# Qwiic_Grideye.net
KiCad netlist of a schematic drawn in EAGLE
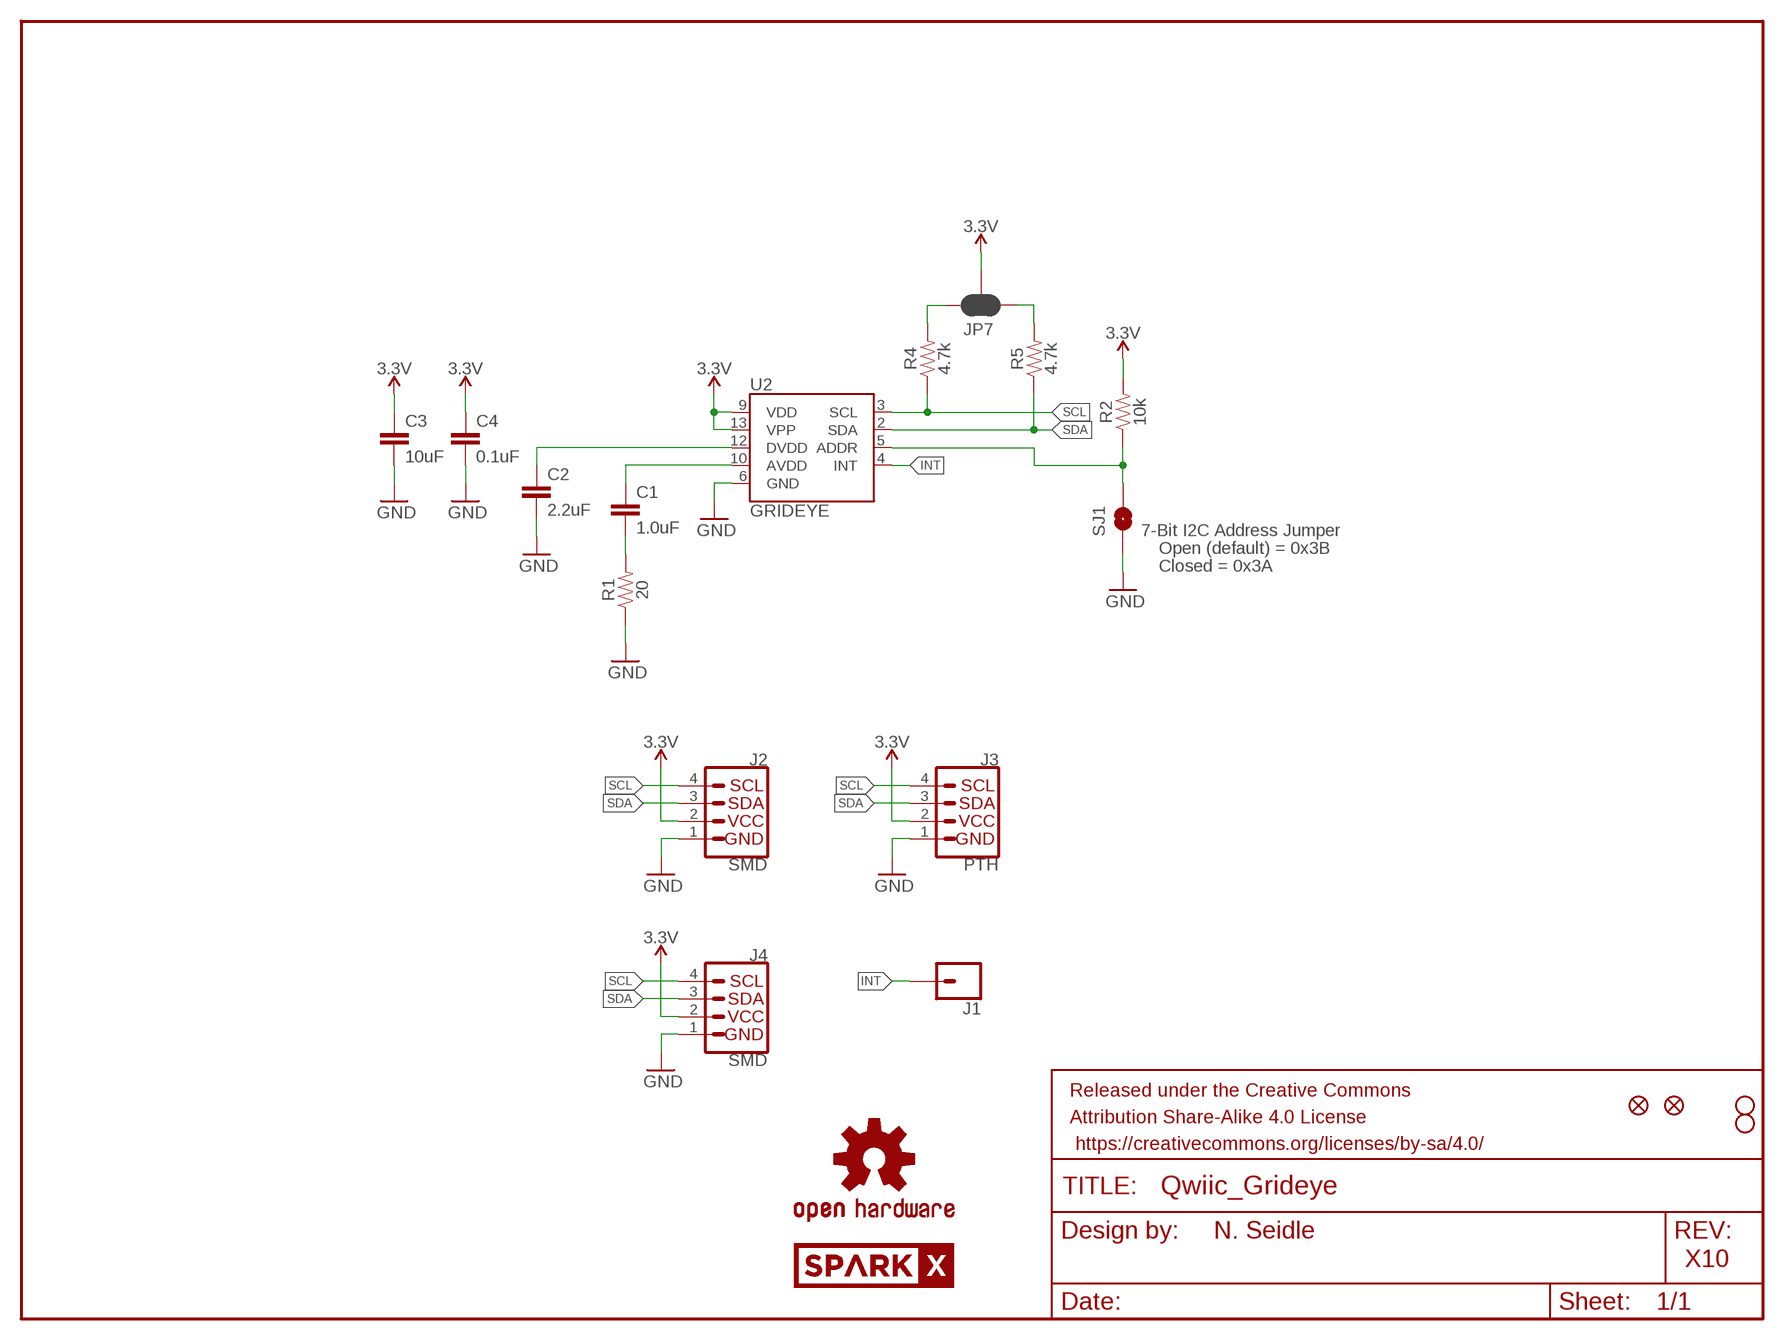
[diagram p0: schematic, sheet 1]

(export (version "E")
  (design (tool "Eeschema 10.0.6"))
  (components
    (comp (ref "C1")
      (value "1.0uF")
      (footprint "eagle-import:0603")
      (libsource (lib "eagle-import") (part "1.0UF-0603-16V-10%"))
    )
    (comp (ref "C2")
      (value "2.2uF")
      (footprint "eagle-import:0603")
      (libsource (lib "eagle-import") (part "2.2UF-0603-10V-20%"))
    )
    (comp (ref "C3")
      (value "10uF")
      (footprint "eagle-import:0603")
      (libsource (lib "eagle-import") (part "10UF-0603-6.3V-20%"))
    )
    (comp (ref "C4")
      (value "0.1uF")
      (footprint "eagle-import:0603")
      (libsource (lib "eagle-import") (part "0.1UF-0603-25V-(+80/-20%)"))
    )
    (comp (ref "FRAME1")
      (value "FRAME-LETTER")
      (footprint "eagle-import:CREATIVE_COMMONS")
      (libsource (lib "eagle-import") (part "FRAME-LETTER"))
    )
    (comp (ref "J1")
      (value "CONN_01PTH_NO_SILK_YES_STOP")
      (footprint "eagle-import:1X01_NO_SILK")
      (libsource (lib "eagle-import") (part "CONN_01PTH_NO_SILK_YES_STOP"))
    )
    (comp (ref "J2")
      (value "SMD")
      (footprint "eagle-import:1X04_1MM_RA")
      (libsource (lib "eagle-import") (part "I2C_STANDARDJS-1MM"))
    )
    (comp (ref "J3")
      (value "PTH")
      (footprint "eagle-import:1X04_NO_SILK")
      (libsource (lib "eagle-import") (part "I2C_STANDARD_NO_SILK"))
    )
    (comp (ref "J4")
      (value "SMD")
      (footprint "eagle-import:1X04_1MM_RA")
      (libsource (lib "eagle-import") (part "I2C_STANDARDJS-1MM"))
    )
    (comp (ref "JP2")
      (value "FIDUCIALUFIDUCIAL")
      (footprint "eagle-import:MICRO-FIDUCIAL")
      (libsource (lib "eagle-import") (part "FIDUCIALUFIDUCIAL"))
    )
    (comp (ref "JP3")
      (value "STAND-OFF")
      (footprint "eagle-import:STAND-OFF")
      (libsource (lib "eagle-import") (part "STAND-OFF"))
    )
    (comp (ref "JP4")
      (value "STAND-OFF")
      (footprint "eagle-import:STAND-OFF")
      (libsource (lib "eagle-import") (part "STAND-OFF"))
    )
    (comp (ref "JP6")
      (value "FIDUCIALUFIDUCIAL")
      (footprint "eagle-import:MICRO-FIDUCIAL")
      (libsource (lib "eagle-import") (part "FIDUCIALUFIDUCIAL"))
    )
    (comp (ref "JP7")
      (value "JUMPER-SMT_3_2-NC_PASTE_SILK")
      (footprint "eagle-import:SMT-JUMPER_3_2-NC_PASTE_SILK")
      (libsource (lib "eagle-import") (part "JUMPER-SMT_3_2-NC_PASTE_SILK"))
    )
    (comp (ref "LOGO1")
      (value "OSHW-LOGOMINI")
      (footprint "eagle-import:OSHW-LOGO-MINI")
      (libsource (lib "eagle-import") (part "OSHW-LOGOMINI"))
    )
    (comp (ref "R1")
      (value "20")
      (footprint "eagle-import:0603")
      (libsource (lib "eagle-import") (part "20OHM-0603-1/10W-1%"))
    )
    (comp (ref "R2")
      (value "10k")
      (footprint "eagle-import:0603")
      (libsource (lib "eagle-import") (part "10KOHM-0603-1/10W-1%"))
    )
    (comp (ref "R4")
      (value "4.7k")
      (footprint "eagle-import:0603")
      (libsource (lib "eagle-import") (part "4.7KOHM-0603-1/10W-1%"))
    )
    (comp (ref "R5")
      (value "4.7k")
      (footprint "eagle-import:0603")
      (libsource (lib "eagle-import") (part "4.7KOHM-0603-1/10W-1%"))
    )
    (comp (ref "SJ1")
      (value "SOLDERJUMPERNO")
      (footprint "eagle-import:SJ_2S-NO")
      (libsource (lib "eagle-import") (part "SOLDERJUMPERNO"))
    )
    (comp (ref "U$1")
      (value "SPARKX-LOGO4")
      (footprint "eagle-import:SPARKX-MEDIUM")
      (libsource (lib "eagle-import") (part "SPARKX-LOGO4"))
    )
    (comp (ref "U$2")
      (value "SPARKX-LOGO4")
      (footprint "eagle-import:SPARKX-MEDIUM")
      (libsource (lib "eagle-import") (part "SPARKX-LOGO4"))
    )
    (comp (ref "U2")
      (value "GRIDEYE")
      (footprint "eagle-import:GRIDEYE-AMG88")
      (libsource (lib "eagle-import") (part "GRIDEYE"))
    )
  )
  (nets
    (net (code "1") (name "3.3V") (class "Default")
      (node (ref "C3") (pin "1") (pinfunction "1_1") (pintype "passive"))
      (node (ref "C4") (pin "1") (pinfunction "1_1") (pintype "passive"))
      (node (ref "J2") (pin "2") (pinfunction "VCC_2") (pintype "power_in"))
      (node (ref "J3") (pin "2") (pinfunction "VCC_2") (pintype "power_in"))
      (node (ref "J4") (pin "2") (pinfunction "VCC_2") (pintype "power_in"))
      (node (ref "JP7") (pin "2") (pinfunction "2_2") (pintype "passive"))
      (node (ref "R2") (pin "2") (pinfunction "2_2") (pintype "passive"))
      (node (ref "U2") (pin "13") (pinfunction "VPP_13") (pintype "bidirectional"))
      (node (ref "U2") (pin "9") (pinfunction "VDD_9") (pintype "bidirectional"))
    )
    (net (code "2") (name "GND") (class "Default")
      (node (ref "C2") (pin "2") (pinfunction "2_2") (pintype "passive"))
      (node (ref "C3") (pin "2") (pinfunction "2_2") (pintype "passive"))
      (node (ref "C4") (pin "2") (pinfunction "2_2") (pintype "passive"))
      (node (ref "J2") (pin "1") (pinfunction "GND_1") (pintype "power_in"))
      (node (ref "J3") (pin "1") (pinfunction "GND_1") (pintype "power_in"))
      (node (ref "J4") (pin "1") (pinfunction "GND_1") (pintype "power_in"))
      (node (ref "R1") (pin "1") (pinfunction "1_1") (pintype "passive"))
      (node (ref "SJ1") (pin "1") (pinfunction "1_1") (pintype "passive"))
      (node (ref "U2") (pin "6") (pinfunction "GND_6") (pintype "bidirectional"))
    )
    (net (code "3") (name "INT") (class "Default")
      (node (ref "J1") (pin "1") (pinfunction "1_1") (pintype "passive"))
      (node (ref "U2") (pin "4") (pinfunction "INT_4") (pintype "bidirectional"))
    )
    (net (code "4") (name "Net-(C1-Pad2)") (class "Default")
      (node (ref "C1") (pin "2") (pinfunction "2_2") (pintype "passive"))
      (node (ref "R1") (pin "2") (pinfunction "2_2") (pintype "passive"))
    )
    (net (code "5") (name "Net-(JP7-Pad1)") (class "Default")
      (node (ref "JP7") (pin "1") (pinfunction "1_1") (pintype "passive"))
      (node (ref "R5") (pin "2") (pinfunction "2_2") (pintype "passive"))
    )
    (net (code "6") (name "Net-(JP7-Pad3)") (class "Default")
      (node (ref "JP7") (pin "3") (pinfunction "3_3") (pintype "passive"))
      (node (ref "R4") (pin "2") (pinfunction "2_2") (pintype "passive"))
    )
    (net (code "7") (name "Net-(U2-ADDR)") (class "Default")
      (node (ref "R2") (pin "1") (pinfunction "1_1") (pintype "passive"))
      (node (ref "SJ1") (pin "2") (pinfunction "2_2") (pintype "passive"))
      (node (ref "U2") (pin "5") (pinfunction "ADDR_5") (pintype "bidirectional"))
    )
    (net (code "8") (name "Net-(U2-AVDD)") (class "Default")
      (node (ref "C1") (pin "1") (pinfunction "1_1") (pintype "passive"))
      (node (ref "U2") (pin "10") (pinfunction "AVDD_10") (pintype "bidirectional"))
    )
    (net (code "9") (name "Net-(U2-DVDD)") (class "Default")
      (node (ref "C2") (pin "1") (pinfunction "1_1") (pintype "passive"))
      (node (ref "U2") (pin "12") (pinfunction "DVDD_12") (pintype "bidirectional"))
    )
    (net (code "10") (name "SCL") (class "Default")
      (node (ref "J2") (pin "4") (pinfunction "SCL_4") (pintype "passive"))
      (node (ref "J3") (pin "4") (pinfunction "SCL_4") (pintype "passive"))
      (node (ref "J4") (pin "4") (pinfunction "SCL_4") (pintype "passive"))
      (node (ref "R4") (pin "1") (pinfunction "1_1") (pintype "passive"))
      (node (ref "U2") (pin "3") (pinfunction "SCL_3") (pintype "bidirectional"))
    )
    (net (code "11") (name "SDA") (class "Default")
      (node (ref "J2") (pin "3") (pinfunction "SDA_3") (pintype "passive"))
      (node (ref "J3") (pin "3") (pinfunction "SDA_3") (pintype "passive"))
      (node (ref "J4") (pin "3") (pinfunction "SDA_3") (pintype "passive"))
      (node (ref "R5") (pin "1") (pinfunction "1_1") (pintype "passive"))
      (node (ref "U2") (pin "2") (pinfunction "SDA_2") (pintype "bidirectional"))
    )
  )
)
